# Rover_Science_Card_V1.net
KiCad netlist of a schematic drawn in Altium Designer
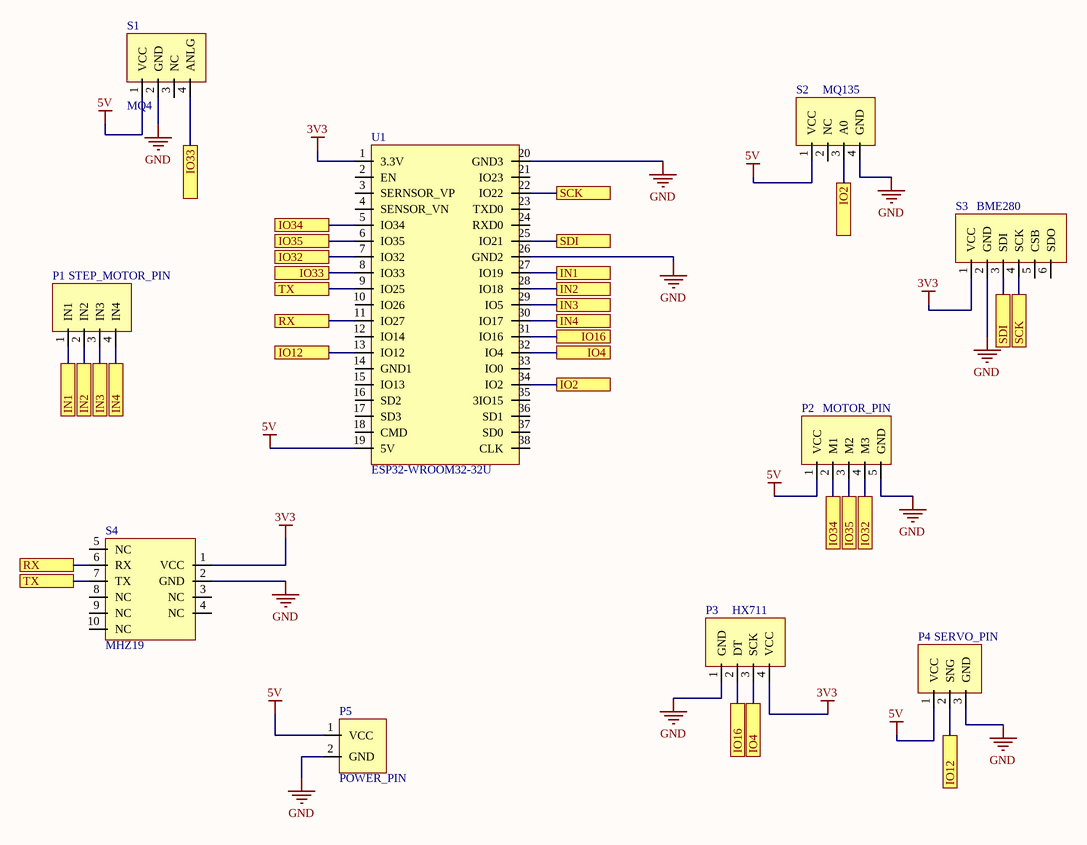
[diagram p0: Rover_Science_Card_V1.SchDoc]

(export (version "E")
  (design (tool "Eeschema 10.0.6"))
  (components
    (comp (ref "P1")
      (value "STEP_MOTOR_PIN")
      (footprint "HX711")
      (libsource (lib "Rover_Science_Card_V1") (part "STEP_MOTOR_PIN"))
    )
    (comp (ref "P2")
      (value "MOTOR_PIN")
      (footprint "Motor_PIN")
      (libsource (lib "Rover_Science_Card_V1") (part "MOTOR_PIN"))
    )
    (comp (ref "P3")
      (value "HX711")
      (footprint "HX711")
      (libsource (lib "Rover_Science_Card_V1") (part "HX711"))
    )
    (comp (ref "P4")
      (value "SERVO_PIN")
      (footprint "Servo PIN")
      (libsource (lib "Rover_Science_Card_V1") (part "SERVO_PIN"))
    )
    (comp (ref "P5")
      (value "POWER_PIN")
      (footprint "POWER")
      (libsource (lib "Rover_Science_Card_V1") (part "POWER_PIN"))
    )
    (comp (ref "S1") (value "MQ4") (footprint "MQ4") (libsource (lib "Rover_Science_Card_V1") (part "MQ4")))
    (comp (ref "S2")
      (value "MQ135")
      (footprint "MQ135")
      (libsource (lib "Rover_Science_Card_V1") (part "MQ135"))
    )
    (comp (ref "S3")
      (value "BME280")
      (footprint "BME280")
      (libsource (lib "Rover_Science_Card_V1") (part "BME280"))
    )
    (comp (ref "S4")
      (value "MHZ19")
      (footprint "MHZ19")
      (libsource (lib "Rover_Science_Card_V1") (part "MHZ19"))
    )
    (comp (ref "U1")
      (value "ESP32-WROOM32-32U")
      (footprint "ESP32-WROOM-32U")
      (libsource (lib "Rover_Science_Card_V1") (part "ESP32-WROOM32-32U"))
    )
  )
  (nets
    (net (code "1") (name "/IN1") (class "Default")
      (node (ref "P1") (pin "1") (pinfunction "IN1_1") (pintype "passive"))
      (node (ref "U1") (pin "27") (pinfunction "IO19_27") (pintype "passive"))
    )
    (net (code "2") (name "/IN2") (class "Default")
      (node (ref "P1") (pin "2") (pinfunction "IN2_2") (pintype "passive"))
      (node (ref "U1") (pin "28") (pinfunction "IO18_28") (pintype "passive"))
    )
    (net (code "3") (name "/IN3") (class "Default")
      (node (ref "P1") (pin "3") (pinfunction "IN3_3") (pintype "passive"))
      (node (ref "U1") (pin "29") (pinfunction "IO5_29") (pintype "passive"))
    )
    (net (code "4") (name "/IN4") (class "Default")
      (node (ref "P1") (pin "4") (pinfunction "IN4_4") (pintype "passive"))
      (node (ref "U1") (pin "30") (pinfunction "IO17_30") (pintype "passive"))
    )
    (net (code "5") (name "/IO2") (class "Default")
      (node (ref "S2") (pin "3") (pinfunction "A0_3") (pintype "passive"))
      (node (ref "U1") (pin "34") (pinfunction "IO2_34") (pintype "passive"))
    )
    (net (code "6") (name "/IO4") (class "Default")
      (node (ref "P3") (pin "3") (pinfunction "SCK_3") (pintype "passive"))
      (node (ref "U1") (pin "32") (pinfunction "IO4_32") (pintype "passive"))
    )
    (net (code "7") (name "/IO12") (class "Default")
      (node (ref "P4") (pin "2") (pinfunction "SNG_2") (pintype "passive"))
      (node (ref "U1") (pin "13") (pinfunction "IO12_13") (pintype "passive"))
    )
    (net (code "8") (name "/IO16") (class "Default")
      (node (ref "P3") (pin "2") (pinfunction "DT_2") (pintype "passive"))
      (node (ref "U1") (pin "31") (pinfunction "IO16_31") (pintype "passive"))
    )
    (net (code "9") (name "/IO32") (class "Default")
      (node (ref "P2") (pin "4") (pinfunction "M3_4") (pintype "passive"))
      (node (ref "U1") (pin "7") (pinfunction "IO32_7") (pintype "passive"))
    )
    (net (code "10") (name "/IO33") (class "Default")
      (node (ref "S1") (pin "4") (pinfunction "ANLG_4") (pintype "passive"))
      (node (ref "U1") (pin "8") (pinfunction "IO33_8") (pintype "passive"))
    )
    (net (code "11") (name "/IO34") (class "Default")
      (node (ref "P2") (pin "2") (pinfunction "M1_2") (pintype "passive"))
      (node (ref "U1") (pin "5") (pinfunction "IO34_5") (pintype "passive"))
    )
    (net (code "12") (name "/IO35") (class "Default")
      (node (ref "P2") (pin "3") (pinfunction "M2_3") (pintype "passive"))
      (node (ref "U1") (pin "6") (pinfunction "IO35_6") (pintype "passive"))
    )
    (net (code "13") (name "/RX") (class "Default")
      (node (ref "S4") (pin "6") (pinfunction "RX_6") (pintype "passive"))
      (node (ref "U1") (pin "11") (pinfunction "IO27_11") (pintype "passive"))
    )
    (net (code "14") (name "/SCK") (class "Default")
      (node (ref "S3") (pin "4") (pinfunction "SCK_4") (pintype "passive"))
      (node (ref "U1") (pin "22") (pinfunction "IO22_22") (pintype "passive"))
    )
    (net (code "15") (name "/SDI") (class "Default")
      (node (ref "S3") (pin "3") (pinfunction "SDI_3") (pintype "passive"))
      (node (ref "U1") (pin "25") (pinfunction "IO21_25") (pintype "passive"))
    )
    (net (code "16") (name "/TX") (class "Default")
      (node (ref "S4") (pin "7") (pinfunction "TX_7") (pintype "passive"))
      (node (ref "U1") (pin "9") (pinfunction "IO25_9") (pintype "passive"))
    )
    (net (code "17") (name "3V3") (class "Default")
      (node (ref "P3") (pin "4") (pinfunction "VCC_4") (pintype "passive"))
      (node (ref "S3") (pin "1") (pinfunction "VCC_1") (pintype "passive"))
      (node (ref "S4") (pin "1") (pinfunction "VCC_1") (pintype "passive"))
      (node (ref "U1") (pin "1") (pinfunction "3.3V_1") (pintype "passive"))
    )
    (net (code "18") (name "5V") (class "Default")
      (node (ref "P2") (pin "1") (pinfunction "VCC_1") (pintype "passive"))
      (node (ref "P4") (pin "1") (pinfunction "VCC_1") (pintype "passive"))
      (node (ref "P5") (pin "1") (pinfunction "VCC_1") (pintype "passive"))
      (node (ref "S1") (pin "1") (pinfunction "VCC_1") (pintype "passive"))
      (node (ref "S2") (pin "1") (pinfunction "VCC_1") (pintype "passive"))
      (node (ref "U1") (pin "19") (pinfunction "5V_19") (pintype "passive"))
    )
    (net (code "19") (name "GND") (class "Default")
      (node (ref "P2") (pin "5") (pinfunction "GND_5") (pintype "passive"))
      (node (ref "P3") (pin "1") (pinfunction "GND_1") (pintype "passive"))
      (node (ref "P4") (pin "3") (pinfunction "GND_3") (pintype "passive"))
      (node (ref "P5") (pin "2") (pinfunction "GND_2") (pintype "passive"))
      (node (ref "S1") (pin "2") (pinfunction "GND_2") (pintype "passive"))
      (node (ref "S2") (pin "4") (pinfunction "GND_4") (pintype "passive"))
      (node (ref "S3") (pin "2") (pinfunction "GND_2") (pintype "passive"))
      (node (ref "S4") (pin "2") (pinfunction "GND_2") (pintype "passive"))
      (node (ref "U1") (pin "20") (pinfunction "GND3_20") (pintype "passive"))
      (node (ref "U1") (pin "26") (pinfunction "GND2_26") (pintype "passive"))
    )
    (net (code "20") (name "unconnected-(S1-NC-Pad3)") (class "Default")
      (node (ref "S1") (pin "3") (pinfunction "NC_3") (pintype "passive"))
    )
    (net (code "21") (name "unconnected-(S2-NC-Pad2)") (class "Default")
      (node (ref "S2") (pin "2") (pinfunction "NC_2") (pintype "passive"))
    )
    (net (code "22") (name "unconnected-(S3-CSB-Pad5)") (class "Default")
      (node (ref "S3") (pin "5") (pinfunction "CSB_5") (pintype "passive"))
    )
    (net (code "23") (name "unconnected-(S3-SDO-Pad6)") (class "Default")
      (node (ref "S3") (pin "6") (pinfunction "SDO_6") (pintype "passive"))
    )
    (net (code "24") (name "unconnected-(S4-NC-Pad3)") (class "Default")
      (node (ref "S4") (pin "3") (pinfunction "NC_3") (pintype "passive"))
    )
    (net (code "25") (name "unconnected-(S4-NC-Pad4)") (class "Default")
      (node (ref "S4") (pin "4") (pinfunction "NC_4") (pintype "passive"))
    )
    (net (code "26") (name "unconnected-(S4-NC-Pad5)") (class "Default")
      (node (ref "S4") (pin "5") (pinfunction "NC_5") (pintype "passive"))
    )
    (net (code "27") (name "unconnected-(S4-NC-Pad8)") (class "Default")
      (node (ref "S4") (pin "8") (pinfunction "NC_8") (pintype "passive"))
    )
    (net (code "28") (name "unconnected-(S4-NC-Pad9)") (class "Default")
      (node (ref "S4") (pin "9") (pinfunction "NC_9") (pintype "passive"))
    )
    (net (code "29") (name "unconnected-(S4-NC-Pad10)") (class "Default")
      (node (ref "S4") (pin "10") (pinfunction "NC_10") (pintype "passive"))
    )
    (net (code "30") (name "unconnected-(U1-3IO15-Pad35)") (class "Default")
      (node (ref "U1") (pin "35") (pinfunction "3IO15_35") (pintype "passive"))
    )
    (net (code "31") (name "unconnected-(U1-CLK-Pad38)") (class "Default")
      (node (ref "U1") (pin "38") (pinfunction "CLK_38") (pintype "passive"))
    )
    (net (code "32") (name "unconnected-(U1-CMD-Pad18)") (class "Default")
      (node (ref "U1") (pin "18") (pinfunction "CMD_18") (pintype "passive"))
    )
    (net (code "33") (name "unconnected-(U1-EN-Pad2)") (class "Default")
      (node (ref "U1") (pin "2") (pinfunction "EN_2") (pintype "passive"))
    )
    (net (code "34") (name "unconnected-(U1-GND1-Pad14)") (class "Default")
      (node (ref "U1") (pin "14") (pinfunction "GND1_14") (pintype "passive"))
    )
    (net (code "35") (name "unconnected-(U1-IO0-Pad33)") (class "Default")
      (node (ref "U1") (pin "33") (pinfunction "IO0_33") (pintype "passive"))
    )
    (net (code "36") (name "unconnected-(U1-IO13-Pad15)") (class "Default")
      (node (ref "U1") (pin "15") (pinfunction "IO13_15") (pintype "passive"))
    )
    (net (code "37") (name "unconnected-(U1-IO14-Pad12)") (class "Default")
      (node (ref "U1") (pin "12") (pinfunction "IO14_12") (pintype "passive"))
    )
    (net (code "38") (name "unconnected-(U1-IO23-Pad21)") (class "Default")
      (node (ref "U1") (pin "21") (pinfunction "IO23_21") (pintype "passive"))
    )
    (net (code "39") (name "unconnected-(U1-IO26-Pad10)") (class "Default")
      (node (ref "U1") (pin "10") (pinfunction "IO26_10") (pintype "passive"))
    )
    (net (code "40") (name "unconnected-(U1-RXD0-Pad24)") (class "Default")
      (node (ref "U1") (pin "24") (pinfunction "RXD0_24") (pintype "passive"))
    )
    (net (code "41") (name "unconnected-(U1-SD0-Pad37)") (class "Default")
      (node (ref "U1") (pin "37") (pinfunction "SD0_37") (pintype "passive"))
    )
    (net (code "42") (name "unconnected-(U1-SD1-Pad36)") (class "Default")
      (node (ref "U1") (pin "36") (pinfunction "SD1_36") (pintype "passive"))
    )
    (net (code "43") (name "unconnected-(U1-SD2-Pad16)") (class "Default")
      (node (ref "U1") (pin "16") (pinfunction "SD2_16") (pintype "passive"))
    )
    (net (code "44") (name "unconnected-(U1-SD3-Pad17)") (class "Default")
      (node (ref "U1") (pin "17") (pinfunction "SD3_17") (pintype "passive"))
    )
    (net (code "45") (name "unconnected-(U1-SENSOR_VN-Pad4)") (class "Default")
      (node (ref "U1") (pin "4") (pinfunction "SENSOR_VN_4") (pintype "passive"))
    )
    (net (code "46") (name "unconnected-(U1-SERNSOR_VP-Pad3)") (class "Default")
      (node (ref "U1") (pin "3") (pinfunction "SERNSOR_VP_3") (pintype "passive"))
    )
    (net (code "47") (name "unconnected-(U1-TXD0-Pad23)") (class "Default")
      (node (ref "U1") (pin "23") (pinfunction "TXD0_23") (pintype "passive"))
    )
  )
)
